# combo_10_01_2017.net
KiCad netlist of a schematic drawn in EAGLE
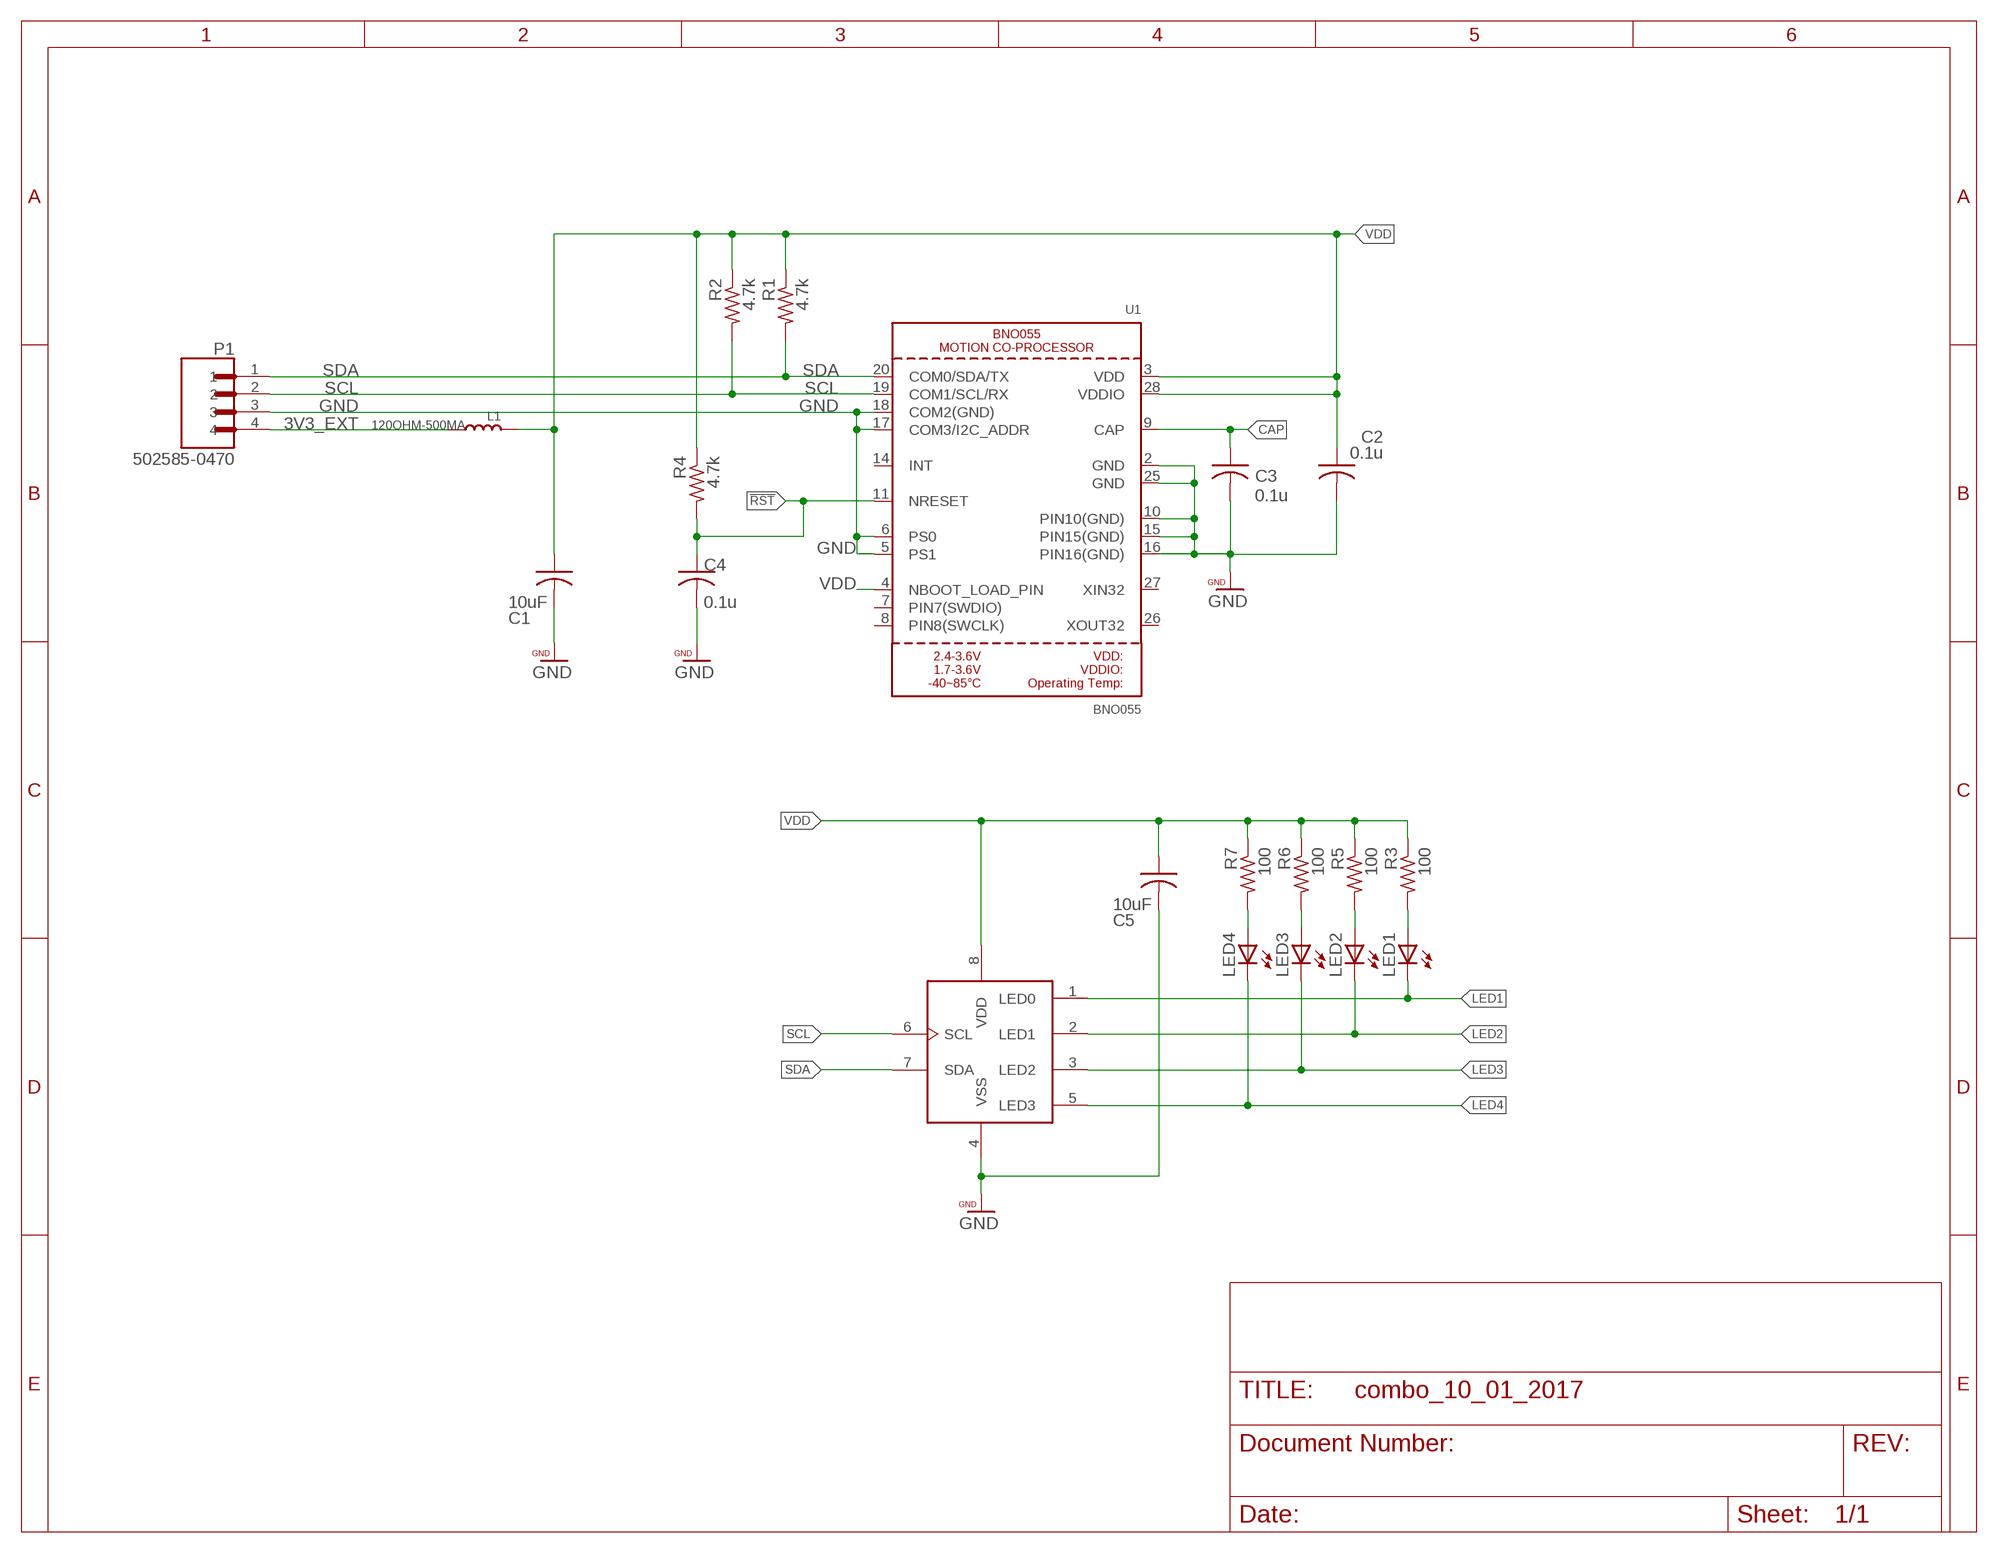
[diagram p0: schematic, sheet 1]

(export (version "E")
  (design (tool "Eeschema 10.0.6"))
  (components
    (comp (ref "C1")
      (value "10uF")
      (footprint "eagle-import:C0402")
      (libsource (lib "eagle-import") (part "C-USC0402"))
    )
    (comp (ref "C2")
      (value "0.1u")
      (footprint "eagle-import:C0402")
      (libsource (lib "eagle-import") (part "C-USC0402"))
    )
    (comp (ref "C3")
      (value "0.1u")
      (footprint "eagle-import:C0402")
      (libsource (lib "eagle-import") (part "C-USC0402"))
    )
    (comp (ref "C4")
      (value "0.1u")
      (footprint "eagle-import:C0402")
      (libsource (lib "eagle-import") (part "C-USC0402"))
    )
    (comp (ref "C5")
      (value "10uF")
      (footprint "eagle-import:C0402")
      (libsource (lib "eagle-import") (part "C-USC0402"))
    )
    (comp (ref "L1")
      (value "120OHM-500MA")
      (footprint "eagle-import:L0603")
      (fields (field (name "MPN") "BLM18AG121SN1D"))
      (libsource (lib "eagle-import") (part "SMD-FERRITE-CHIP-120-OHM-500MA(0603)"))
    )
    (comp (ref "LED1")
      (value "LEDCHIP-LED0603")
      (footprint "eagle-import:CHIP-LED0603")
      (libsource (lib "eagle-import") (part "LEDCHIP-LED0603"))
    )
    (comp (ref "LED2")
      (value "LEDCHIP-LED0603")
      (footprint "eagle-import:CHIP-LED0603")
      (libsource (lib "eagle-import") (part "LEDCHIP-LED0603"))
    )
    (comp (ref "LED3")
      (value "LEDCHIP-LED0603")
      (footprint "eagle-import:CHIP-LED0603")
      (libsource (lib "eagle-import") (part "LEDCHIP-LED0603"))
    )
    (comp (ref "LED4")
      (value "LEDCHIP-LED0603")
      (footprint "eagle-import:CHIP-LED0603")
      (libsource (lib "eagle-import") (part "LEDCHIP-LED0603"))
    )
    (comp (ref "P1")
      (value "502585-0470")
      (footprint "eagle-import:MOLEX_502585-0470")
      (fields (field (name "MF") "Molex"))
      (libsource (lib "eagle-import") (part "502585-0470"))
    )
    (comp (ref "R1")
      (value "4.7k")
      (footprint "eagle-import:R0402")
      (libsource (lib "eagle-import") (part "R-US_R0402"))
    )
    (comp (ref "R2")
      (value "4.7k")
      (footprint "eagle-import:R0402")
      (libsource (lib "eagle-import") (part "R-US_R0402"))
    )
    (comp (ref "R3")
      (value "100")
      (footprint "eagle-import:R0402")
      (libsource (lib "eagle-import") (part "R-US_R0402"))
    )
    (comp (ref "R4")
      (value "4.7k")
      (footprint "eagle-import:R0402")
      (libsource (lib "eagle-import") (part "R-US_R0402"))
    )
    (comp (ref "R5")
      (value "100")
      (footprint "eagle-import:R0402")
      (libsource (lib "eagle-import") (part "R-US_R0402"))
    )
    (comp (ref "R6")
      (value "100")
      (footprint "eagle-import:R0402")
      (libsource (lib "eagle-import") (part "R-US_R0402"))
    )
    (comp (ref "R7")
      (value "100")
      (footprint "eagle-import:R0402")
      (libsource (lib "eagle-import") (part "R-US_R0402"))
    )
    (comp (ref "U1")
      (value "BNO055")
      (footprint "eagle-import:BNO055")
      (libsource (lib "eagle-import") (part "BNO055"))
    )
    (comp (ref "U2")
      (value "PCA9533DP")
      (footprint "eagle-import:TSSOP8")
      (libsource (lib "eagle-import") (part "PCA9533DP"))
    )
  )
  (nets
    (net (code "1") (name "/3V3_EXT") (class "Default")
      (node (ref "L1") (pin "2") (pinfunction "2_2") (pintype "passive"))
      (node (ref "P1") (pin "4") (pinfunction "4_4") (pintype "passive"))
    )
    (net (code "2") (name "/~{RST}") (class "Default")
      (node (ref "C4") (pin "1") (pinfunction "1_1") (pintype "passive"))
      (node (ref "R4") (pin "2") (pinfunction "2_2") (pintype "passive"))
      (node (ref "U1") (pin "11") (pinfunction "NRESET_11") (pintype "bidirectional"))
    )
    (net (code "3") (name "CAP") (class "Default")
      (node (ref "C3") (pin "1") (pinfunction "1_1") (pintype "passive"))
      (node (ref "U1") (pin "9") (pinfunction "CAP_9") (pintype "passive"))
    )
    (net (code "4") (name "GND") (class "Default")
      (node (ref "C1") (pin "2") (pinfunction "2_2") (pintype "passive"))
      (node (ref "C2") (pin "2") (pinfunction "2_2") (pintype "passive"))
      (node (ref "C3") (pin "2") (pinfunction "2_2") (pintype "passive"))
      (node (ref "C4") (pin "2") (pinfunction "2_2") (pintype "passive"))
      (node (ref "C5") (pin "2") (pinfunction "2_2") (pintype "passive"))
      (node (ref "P1") (pin "3") (pinfunction "3_3") (pintype "passive"))
      (node (ref "U1") (pin "10") (pinfunction "PIN10(GND)_10") (pintype "bidirectional"))
      (node (ref "U1") (pin "15") (pinfunction "PIN15(GND)_15") (pintype "bidirectional"))
      (node (ref "U1") (pin "16") (pinfunction "PIN16(GND)_16") (pintype "bidirectional"))
      (node (ref "U1") (pin "17") (pinfunction "COM3/I2C_ADDR_17") (pintype "bidirectional"))
      (node (ref "U1") (pin "18") (pinfunction "COM2(GND)_18") (pintype "bidirectional"))
      (node (ref "U1") (pin "2") (pinfunction "GND_2") (pintype "power_in"))
      (node (ref "U1") (pin "25") (pinfunction "GND_25") (pintype "power_in"))
      (node (ref "U1") (pin "5") (pinfunction "PS1_5") (pintype "input"))
      (node (ref "U1") (pin "6") (pinfunction "PS0_6") (pintype "input"))
      (node (ref "U2") (pin "4") (pinfunction "VSS_4") (pintype "power_in"))
    )
    (net (code "5") (name "LED1") (class "Default")
      (node (ref "LED1") (pin "C") (pinfunction "C_C") (pintype "passive"))
      (node (ref "U2") (pin "1") (pinfunction "LED0_1") (pintype "bidirectional"))
    )
    (net (code "6") (name "LED2") (class "Default")
      (node (ref "LED2") (pin "C") (pinfunction "C_C") (pintype "passive"))
      (node (ref "U2") (pin "2") (pinfunction "LED1_2") (pintype "bidirectional"))
    )
    (net (code "7") (name "LED3") (class "Default")
      (node (ref "LED3") (pin "C") (pinfunction "C_C") (pintype "passive"))
      (node (ref "U2") (pin "3") (pinfunction "LED2_3") (pintype "bidirectional"))
    )
    (net (code "8") (name "LED4") (class "Default")
      (node (ref "LED4") (pin "C") (pinfunction "C_C") (pintype "passive"))
      (node (ref "U2") (pin "5") (pinfunction "LED3_5") (pintype "bidirectional"))
    )
    (net (code "9") (name "Net-(LED1-PadA)") (class "Default")
      (node (ref "LED1") (pin "A") (pinfunction "A_A") (pintype "passive"))
      (node (ref "R3") (pin "2") (pinfunction "2_2") (pintype "passive"))
    )
    (net (code "10") (name "Net-(LED2-PadA)") (class "Default")
      (node (ref "LED2") (pin "A") (pinfunction "A_A") (pintype "passive"))
      (node (ref "R5") (pin "2") (pinfunction "2_2") (pintype "passive"))
    )
    (net (code "11") (name "Net-(LED3-PadA)") (class "Default")
      (node (ref "LED3") (pin "A") (pinfunction "A_A") (pintype "passive"))
      (node (ref "R6") (pin "2") (pinfunction "2_2") (pintype "passive"))
    )
    (net (code "12") (name "Net-(LED4-PadA)") (class "Default")
      (node (ref "LED4") (pin "A") (pinfunction "A_A") (pintype "passive"))
      (node (ref "R7") (pin "2") (pinfunction "2_2") (pintype "passive"))
    )
    (net (code "13") (name "SCL") (class "Default")
      (node (ref "P1") (pin "2") (pinfunction "2_2") (pintype "passive"))
      (node (ref "R2") (pin "2") (pinfunction "2_2") (pintype "passive"))
      (node (ref "U1") (pin "19") (pinfunction "COM1/SCL/RX_19") (pintype "bidirectional"))
      (node (ref "U2") (pin "6") (pinfunction "SCL_6") (pintype "input"))
    )
    (net (code "14") (name "SDA") (class "Default")
      (node (ref "P1") (pin "1") (pinfunction "1_1") (pintype "passive"))
      (node (ref "R1") (pin "2") (pinfunction "2_2") (pintype "passive"))
      (node (ref "U1") (pin "20") (pinfunction "COM0/SDA/TX_20") (pintype "bidirectional"))
      (node (ref "U2") (pin "7") (pinfunction "SDA_7") (pintype "bidirectional"))
    )
    (net (code "15") (name "VDD") (class "Default")
      (node (ref "C1") (pin "1") (pinfunction "1_1") (pintype "passive"))
      (node (ref "C2") (pin "1") (pinfunction "1_1") (pintype "passive"))
      (node (ref "C5") (pin "1") (pinfunction "1_1") (pintype "passive"))
      (node (ref "L1") (pin "1") (pinfunction "1_1") (pintype "passive"))
      (node (ref "R1") (pin "1") (pinfunction "1_1") (pintype "passive"))
      (node (ref "R2") (pin "1") (pinfunction "1_1") (pintype "passive"))
      (node (ref "R3") (pin "1") (pinfunction "1_1") (pintype "passive"))
      (node (ref "R4") (pin "1") (pinfunction "1_1") (pintype "passive"))
      (node (ref "R5") (pin "1") (pinfunction "1_1") (pintype "passive"))
      (node (ref "R6") (pin "1") (pinfunction "1_1") (pintype "passive"))
      (node (ref "R7") (pin "1") (pinfunction "1_1") (pintype "passive"))
      (node (ref "U1") (pin "28") (pinfunction "VDDIO_28") (pintype "power_in"))
      (node (ref "U1") (pin "3") (pinfunction "VDD_3") (pintype "power_in"))
      (node (ref "U1") (pin "4") (pinfunction "NBOOT_LOAD_PIN_4") (pintype "bidirectional"))
      (node (ref "U2") (pin "8") (pinfunction "VDD_8") (pintype "power_in"))
    )
    (net (code "16") (name "unconnected-(U1-INT-Pad14)") (class "Default")
      (node (ref "U1") (pin "14") (pinfunction "INT_14") (pintype "output"))
    )
    (net (code "17") (name "unconnected-(U1-PIN7(SWDIO)-Pad7)") (class "Default")
      (node (ref "U1") (pin "7") (pinfunction "PIN7(SWDIO)_7") (pintype "bidirectional"))
    )
    (net (code "18") (name "unconnected-(U1-PIN8(SWCLK)-Pad8)") (class "Default")
      (node (ref "U1") (pin "8") (pinfunction "PIN8(SWCLK)_8") (pintype "bidirectional"))
    )
    (net (code "19") (name "unconnected-(U1-XIN32-Pad27)") (class "Default")
      (node (ref "U1") (pin "27") (pinfunction "XIN32_27") (pintype "input"))
    )
    (net (code "20") (name "unconnected-(U1-XOUT32-Pad26)") (class "Default")
      (node (ref "U1") (pin "26") (pinfunction "XOUT32_26") (pintype "output"))
    )
  )
)
